# Power_5V-4A_12V-1A.net
KiCad netlist of a schematic drawn in EAGLE
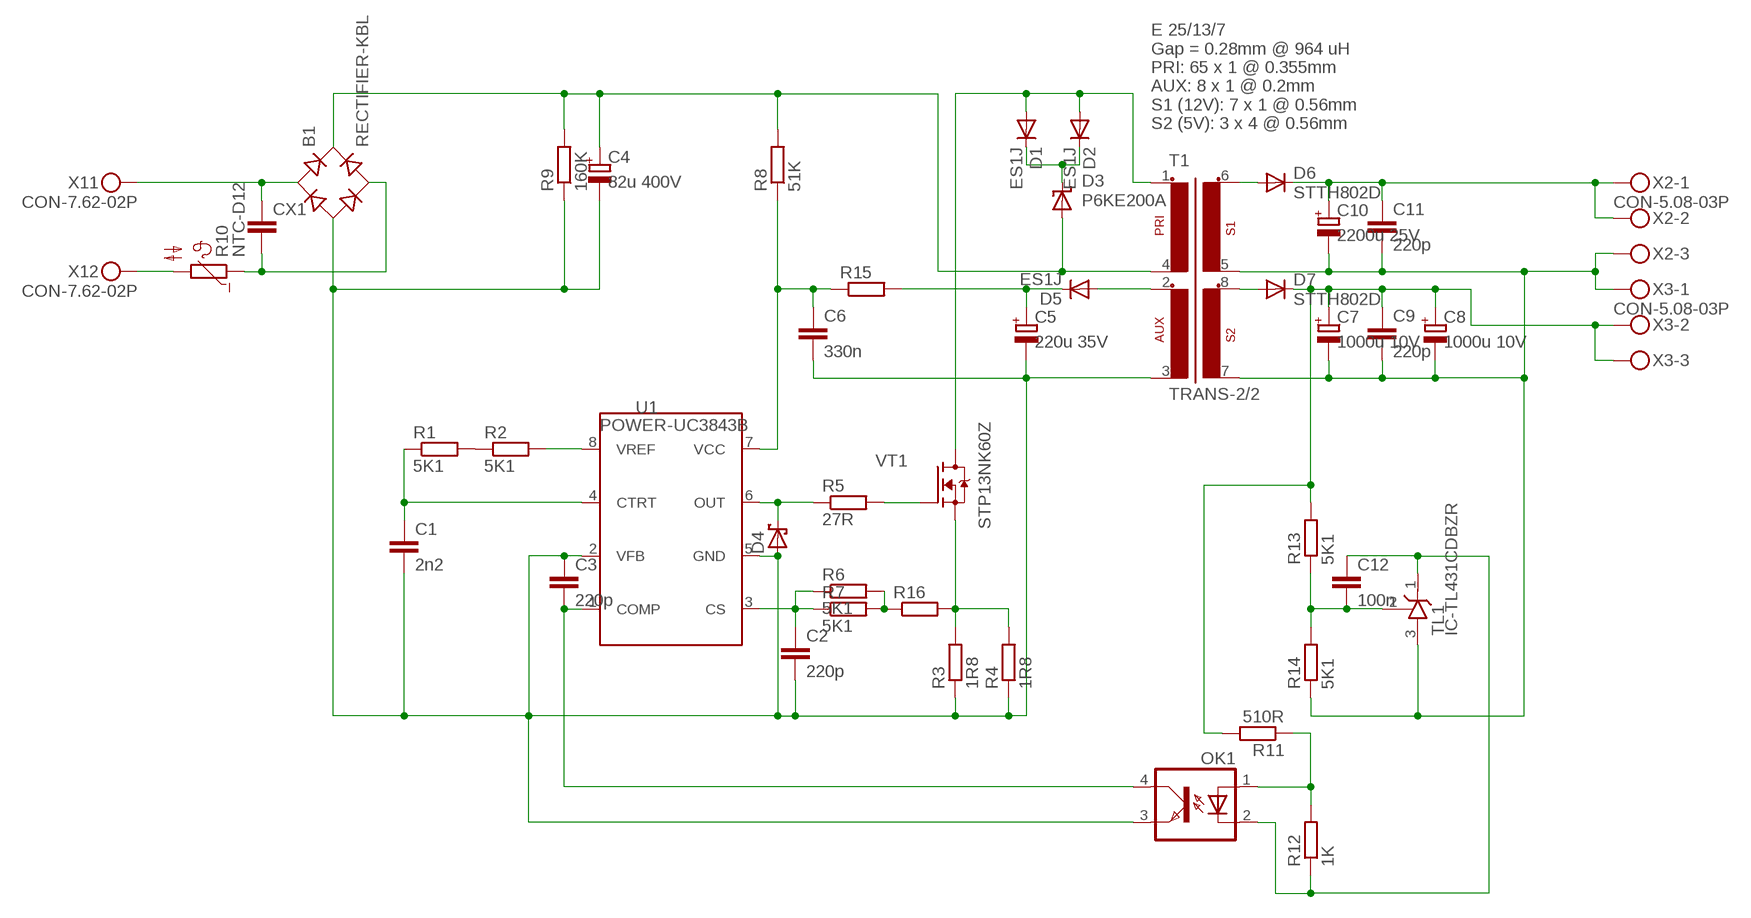
[diagram p0: schematic, sheet 1]

(export (version "E")
  (design (tool "Eeschema 10.0.6"))
  (components
    (comp (ref "B1")
      (value "RECTIFIER-KBL")
      (footprint "eagle-import:KBL")
      (libsource (lib "eagle-import") (part "RECTIFIER-KBL"))
    )
    (comp (ref "C1")
      (value "2n2")
      (footprint "eagle-import:CAP0603")
      (libsource (lib "eagle-import") (part "CAP_0603"))
    )
    (comp (ref "C2")
      (value "220p")
      (footprint "eagle-import:CAP1206")
      (libsource (lib "eagle-import") (part "CAP_1206"))
    )
    (comp (ref "C3")
      (value "220p")
      (footprint "eagle-import:CAP1206")
      (libsource (lib "eagle-import") (part "CAP_1206"))
    )
    (comp (ref "C4")
      (value "82u 400V")
      (footprint "eagle-import:C_D25-G10-CLAMP")
      (libsource (lib "eagle-import") (part "CAP-POL_E25-10-C"))
    )
    (comp (ref "C5")
      (value "220u 35V")
      (footprint "eagle-import:E3,5-8")
      (libsource (lib "eagle-import") (part "CAP-POL_E3.5-8"))
    )
    (comp (ref "C6")
      (value "330n")
      (footprint "eagle-import:CAP1206")
      (libsource (lib "eagle-import") (part "CAP_1206"))
    )
    (comp (ref "C7")
      (value "1000u 10V")
      (footprint "eagle-import:E5-10,5")
      (libsource (lib "eagle-import") (part "CAP-POL_E5-10.5"))
    )
    (comp (ref "C8")
      (value "1000u 10V")
      (footprint "eagle-import:E5-10,5")
      (libsource (lib "eagle-import") (part "CAP-POL_E5-10.5"))
    )
    (comp (ref "C9")
      (value "220p")
      (footprint "eagle-import:CAP1206")
      (libsource (lib "eagle-import") (part "CAP_1206"))
    )
    (comp (ref "C10")
      (value "2200u 25V")
      (footprint "eagle-import:E5-10,5")
      (libsource (lib "eagle-import") (part "CAP-POL_E5-10.5"))
    )
    (comp (ref "C11")
      (value "220p")
      (footprint "eagle-import:CAP1206")
      (libsource (lib "eagle-import") (part "CAP_1206"))
    )
    (comp (ref "C12")
      (value "100n")
      (footprint "eagle-import:CAP0805")
      (libsource (lib "eagle-import") (part "CAP_0805"))
    )
    (comp (ref "CX1")
      (value "CXXC15B6")
      (footprint "eagle-import:XC15B6")
      (libsource (lib "eagle-import") (part "CXXC15B6"))
    )
    (comp (ref "D1")
      (value "ES1J")
      (footprint "eagle-import:DO214AC")
      (libsource (lib "eagle-import") (part "DIODE_ES1J"))
    )
    (comp (ref "D2")
      (value "ES1J")
      (footprint "eagle-import:DO214AC")
      (libsource (lib "eagle-import") (part "DIODE_ES1J"))
    )
    (comp (ref "D3")
      (value "P6KE200A")
      (footprint "eagle-import:DO15-12")
      (libsource (lib "eagle-import") (part "SUPRESSORDO-204AC"))
    )
    (comp (ref "D4")
      (value "DIODE-SH_SMA")
      (footprint "eagle-import:DO214AC")
      (libsource (lib "eagle-import") (part "DIODE-SH_SMA"))
    )
    (comp (ref "D5")
      (value "ES1J")
      (footprint "eagle-import:DO214AC")
      (libsource (lib "eagle-import") (part "DIODE_ES1J"))
    )
    (comp (ref "D6")
      (value "STTH802D")
      (footprint "eagle-import:TO220ACS")
      (libsource (lib "eagle-import") (part "DIODE_TO-220-2"))
    )
    (comp (ref "D7")
      (value "STTH802D")
      (footprint "eagle-import:TO220ACS")
      (libsource (lib "eagle-import") (part "DIODE_TO-220-2"))
    )
    (comp (ref "OK1")
      (value "OPTOTRANSPC817")
      (footprint "eagle-import:DIL04")
      (fields (field (name "MPN") "PC817X4J000F"))
      (libsource (lib "eagle-import") (part "OPTOTRANSPC817"))
    )
    (comp (ref "R1")
      (value "5K1")
      (footprint "eagle-import:RESC1508X50")
      (libsource (lib "eagle-import") (part "R_R0603"))
    )
    (comp (ref "R2")
      (value "5K1")
      (footprint "eagle-import:RESC1508X50")
      (libsource (lib "eagle-import") (part "R_R0603"))
    )
    (comp (ref "R3")
      (value "1R8")
      (footprint "eagle-import:MF-025")
      (libsource (lib "eagle-import") (part "R_MF-025"))
    )
    (comp (ref "R4")
      (value "1R8")
      (footprint "eagle-import:MF-025")
      (libsource (lib "eagle-import") (part "R_MF-025"))
    )
    (comp (ref "R5")
      (value "27R")
      (footprint "eagle-import:RESC3216X60")
      (libsource (lib "eagle-import") (part "R_R1206"))
    )
    (comp (ref "R6")
      (value "5K1")
      (footprint "eagle-import:RESC1508X50")
      (libsource (lib "eagle-import") (part "R_R0603"))
    )
    (comp (ref "R7")
      (value "5K1")
      (footprint "eagle-import:RESC1508X50")
      (libsource (lib "eagle-import") (part "R_R0603"))
    )
    (comp (ref "R8")
      (value "51K")
      (footprint "eagle-import:MF-1")
      (libsource (lib "eagle-import") (part "R_MF-1"))
    )
    (comp (ref "R9")
      (value "160K")
      (footprint "eagle-import:MF-0125")
      (libsource (lib "eagle-import") (part "R_MF-0125"))
    )
    (comp (ref "R10")
      (value "NTC-D12")
      (footprint "eagle-import:NTC-D12")
      (libsource (lib "eagle-import") (part "NTC-D12"))
    )
    (comp (ref "R11")
      (value "510R")
      (footprint "eagle-import:RESC2012X50")
      (libsource (lib "eagle-import") (part "R_R0805"))
    )
    (comp (ref "R12")
      (value "1K")
      (footprint "eagle-import:RESC2012X50")
      (libsource (lib "eagle-import") (part "R_R0805"))
    )
    (comp (ref "R13")
      (value "5K1")
      (footprint "eagle-import:RESC1508X50")
      (libsource (lib "eagle-import") (part "R_R0603"))
    )
    (comp (ref "R14")
      (value "5K1")
      (footprint "eagle-import:RESC1508X50")
      (libsource (lib "eagle-import") (part "R_R0603"))
    )
    (comp (ref "R15")
      (value "R_R0805")
      (footprint "eagle-import:RESC2012X50")
      (libsource (lib "eagle-import") (part "R_R0805"))
    )
    (comp (ref "R16")
      (value "R_R0805")
      (footprint "eagle-import:RESC2012X50")
      (libsource (lib "eagle-import") (part "R_R0805"))
    )
    (comp (ref "T1")
      (value "TRANS-2/2")
      (footprint "eagle-import:EE25_8PIN_HORIZ")
      (libsource (lib "eagle-import") (part "TRANS-2/2"))
    )
    (comp (ref "TL1")
      (value "IC-TL431CDBZR")
      (footprint "eagle-import:SOT95P240X115-3")
      (libsource (lib "eagle-import") (part "IC-TL431CDBZR"))
    )
    (comp (ref "U1")
      (value "POWER-UC3843B")
      (footprint "eagle-import:DIP-8")
      (libsource (lib "eagle-import") (part "POWER-UC3843B"))
    )
    (comp (ref "VT1")
      (value "STP13NK60Z")
      (footprint "eagle-import:TO-220V")
      (libsource (lib "eagle-import") (part "FET-NTO-220"))
    )
    (comp (ref "X1")
      (value "CON-7.62-02P")
      (footprint "eagle-import:KF25C-7.62-02P-13")
      (libsource (lib "eagle-import") (part "CON-7.62-02P"))
    )
    (comp (ref "X2")
      (value "CON-5.08-03P")
      (footprint "eagle-import:MKDSN1,5_3-5,08")
      (libsource (lib "eagle-import") (part "CON-5.08-03P"))
    )
    (comp (ref "X3")
      (value "CON-5.08-03P")
      (footprint "eagle-import:MKDSN1,5_3-5,08")
      (libsource (lib "eagle-import") (part "CON-5.08-03P"))
    )
  )
  (nets
    (net (code "1") (name "Net-(B1-PadAC2)") (class "Default")
      (node (ref "B1") (pin "AC2") (pinfunction "AC2_AC2") (pintype "passive"))
      (node (ref "CX1") (pin "2") (pinfunction "2_2") (pintype "passive"))
      (node (ref "R10") (pin "1") (pinfunction "1_1") (pintype "passive"))
    )
    (net (code "2") (name "Net-(C5-Pad+)") (class "Default")
      (node (ref "C5") (pin "+") (pinfunction "+_+") (pintype "passive"))
      (node (ref "D5") (pin "C") (pinfunction "C_C") (pintype "passive"))
      (node (ref "R15") (pin "2") (pinfunction "2_2") (pintype "passive"))
    )
    (net (code "3") (name "Net-(D1-PadC)") (class "Default")
      (node (ref "D1") (pin "C") (pinfunction "C_C") (pintype "passive"))
      (node (ref "D2") (pin "C") (pinfunction "C_C") (pintype "passive"))
      (node (ref "D3") (pin "C") (pinfunction "C_C") (pintype "passive"))
    )
    (net (code "4") (name "Net-(OK1-A)") (class "Default")
      (node (ref "OK1") (pin "1") (pinfunction "A_1") (pintype "passive"))
      (node (ref "R11") (pin "1") (pinfunction "1_1") (pintype "passive"))
      (node (ref "R12") (pin "2") (pinfunction "2_2") (pintype "passive"))
    )
    (net (code "5") (name "Net-(OK1-C)") (class "Default")
      (node (ref "C12") (pin "1") (pinfunction "1_1") (pintype "passive"))
      (node (ref "OK1") (pin "2") (pinfunction "C_2") (pintype "passive"))
      (node (ref "R12") (pin "1") (pinfunction "1_1") (pintype "passive"))
      (node (ref "TL1") (pin "1") (pinfunction "C_1") (pintype "passive"))
    )
    (net (code "6") (name "Net-(OK1-COL)") (class "Default")
      (node (ref "C3") (pin "2") (pinfunction "2_2") (pintype "passive"))
      (node (ref "OK1") (pin "4") (pinfunction "COL_4") (pintype "passive"))
      (node (ref "U1") (pin "1") (pinfunction "COMP_1") (pintype "bidirectional"))
    )
    (net (code "7") (name "Net-(OK1-EMIT)") (class "Default")
      (node (ref "B1") (pin "-") (pinfunction "-_-") (pintype "passive"))
      (node (ref "C1") (pin "2") (pinfunction "2_2") (pintype "passive"))
      (node (ref "C2") (pin "2") (pinfunction "2_2") (pintype "passive"))
      (node (ref "C3") (pin "1") (pinfunction "1_1") (pintype "passive"))
      (node (ref "C4") (pin "-") (pinfunction "-_-") (pintype "passive"))
      (node (ref "C5") (pin "-") (pinfunction "-_-") (pintype "passive"))
      (node (ref "C6") (pin "2") (pinfunction "2_2") (pintype "passive"))
      (node (ref "D4") (pin "A") (pinfunction "A_A") (pintype "passive"))
      (node (ref "OK1") (pin "3") (pinfunction "EMIT_3") (pintype "passive"))
      (node (ref "R3") (pin "1") (pinfunction "1_1") (pintype "passive"))
      (node (ref "R4") (pin "1") (pinfunction "1_1") (pintype "passive"))
      (node (ref "R9") (pin "1") (pinfunction "1_1") (pintype "passive"))
      (node (ref "T1") (pin "3") (pinfunction "AUX-2_3") (pintype "passive"))
      (node (ref "U1") (pin "2") (pinfunction "VFB_2") (pintype "input"))
      (node (ref "U1") (pin "5") (pinfunction "GND_5") (pintype "power_in"))
    )
    (net (code "8") (name "Net-(R1-Pad2)") (class "Default")
      (node (ref "R1") (pin "2") (pinfunction "2_2") (pintype "passive"))
      (node (ref "R2") (pin "1") (pinfunction "1_1") (pintype "passive"))
    )
    (net (code "9") (name "Net-(R16-Pad1)") (class "Default")
      (node (ref "R16") (pin "1") (pinfunction "1_1") (pintype "passive"))
      (node (ref "R6") (pin "2") (pinfunction "2_2") (pintype "passive"))
      (node (ref "R7") (pin "2") (pinfunction "2_2") (pintype "passive"))
    )
    (net (code "10") (name "Net-(T1-AUX-1)") (class "Default")
      (node (ref "D5") (pin "A") (pinfunction "A_A") (pintype "passive"))
      (node (ref "T1") (pin "2") (pinfunction "AUX-1_2") (pintype "passive"))
    )
    (net (code "11") (name "Net-(T1-P1-1)") (class "Default")
      (node (ref "D1") (pin "A") (pinfunction "A_A") (pintype "passive"))
      (node (ref "D2") (pin "A") (pinfunction "A_A") (pintype "passive"))
      (node (ref "T1") (pin "1") (pinfunction "P1-1_1") (pintype "passive"))
      (node (ref "VT1") (pin "2") (pinfunction "D_2") (pintype "passive"))
    )
    (net (code "12") (name "Net-(T1-P1-2)") (class "Default")
      (node (ref "B1") (pin "+") (pinfunction "+_+") (pintype "passive"))
      (node (ref "C4") (pin "+") (pinfunction "+_+") (pintype "passive"))
      (node (ref "D3") (pin "A") (pinfunction "A_A") (pintype "passive"))
      (node (ref "R8") (pin "2") (pinfunction "2_2") (pintype "passive"))
      (node (ref "R9") (pin "2") (pinfunction "2_2") (pintype "passive"))
      (node (ref "T1") (pin "4") (pinfunction "P1-2_4") (pintype "passive"))
    )
    (net (code "13") (name "Net-(T1-S1-1)") (class "Default")
      (node (ref "D6") (pin "A") (pinfunction "A_A") (pintype "passive"))
      (node (ref "T1") (pin "6") (pinfunction "S1-1_6") (pintype "passive"))
    )
    (net (code "14") (name "Net-(T1-S1-2)") (class "Default")
      (node (ref "C10") (pin "-") (pinfunction "-_-") (pintype "passive"))
      (node (ref "C11") (pin "2") (pinfunction "2_2") (pintype "passive"))
      (node (ref "C7") (pin "-") (pinfunction "-_-") (pintype "passive"))
      (node (ref "C8") (pin "-") (pinfunction "-_-") (pintype "passive"))
      (node (ref "C9") (pin "2") (pinfunction "2_2") (pintype "passive"))
      (node (ref "R14") (pin "1") (pinfunction "1_1") (pintype "passive"))
      (node (ref "T1") (pin "5") (pinfunction "S1-2_5") (pintype "passive"))
      (node (ref "T1") (pin "7") (pinfunction "S2-2_7") (pintype "passive"))
      (node (ref "TL1") (pin "3") (pinfunction "A_3") (pintype "passive"))
      (node (ref "X2") (pin "3") (pinfunction "KL_3") (pintype "passive"))
      (node (ref "X3") (pin "1") (pinfunction "KL_1") (pintype "passive"))
    )
    (net (code "15") (name "Net-(T1-S2-1)") (class "Default")
      (node (ref "D7") (pin "A") (pinfunction "A_A") (pintype "passive"))
      (node (ref "T1") (pin "8") (pinfunction "S2-1_8") (pintype "passive"))
    )
    (net (code "16") (name "Net-(TL1-R)") (class "Default")
      (node (ref "C12") (pin "2") (pinfunction "2_2") (pintype "passive"))
      (node (ref "R13") (pin "1") (pinfunction "1_1") (pintype "passive"))
      (node (ref "R14") (pin "2") (pinfunction "2_2") (pintype "passive"))
      (node (ref "TL1") (pin "2") (pinfunction "R_2") (pintype "passive"))
    )
    (net (code "17") (name "Net-(U1-CS)") (class "Default")
      (node (ref "C2") (pin "1") (pinfunction "1_1") (pintype "passive"))
      (node (ref "R6") (pin "1") (pinfunction "1_1") (pintype "passive"))
      (node (ref "R7") (pin "1") (pinfunction "1_1") (pintype "passive"))
      (node (ref "U1") (pin "3") (pinfunction "CS_3") (pintype "input"))
    )
    (net (code "18") (name "Net-(U1-CTRT)") (class "Default")
      (node (ref "C1") (pin "1") (pinfunction "1_1") (pintype "passive"))
      (node (ref "R1") (pin "1") (pinfunction "1_1") (pintype "passive"))
      (node (ref "U1") (pin "4") (pinfunction "CTRT_4") (pintype "bidirectional"))
    )
    (net (code "19") (name "Net-(U1-OUT)") (class "Default")
      (node (ref "D4") (pin "C") (pinfunction "C_C") (pintype "passive"))
      (node (ref "R5") (pin "1") (pinfunction "1_1") (pintype "passive"))
      (node (ref "U1") (pin "6") (pinfunction "OUT_6") (pintype "output"))
    )
    (net (code "20") (name "Net-(U1-VCC)") (class "Default")
      (node (ref "C6") (pin "1") (pinfunction "1_1") (pintype "passive"))
      (node (ref "R15") (pin "1") (pinfunction "1_1") (pintype "passive"))
      (node (ref "R8") (pin "1") (pinfunction "1_1") (pintype "passive"))
      (node (ref "U1") (pin "7") (pinfunction "VCC_7") (pintype "power_in"))
    )
    (net (code "21") (name "Net-(U1-VREF)") (class "Default")
      (node (ref "R2") (pin "2") (pinfunction "2_2") (pintype "passive"))
      (node (ref "U1") (pin "8") (pinfunction "VREF_8") (pintype "power_in"))
    )
    (net (code "22") (name "Net-(VT1-G)") (class "Default")
      (node (ref "R5") (pin "2") (pinfunction "2_2") (pintype "passive"))
      (node (ref "VT1") (pin "1") (pinfunction "G_1") (pintype "passive"))
    )
    (net (code "23") (name "Net-(VT1-S)") (class "Default")
      (node (ref "R16") (pin "2") (pinfunction "2_2") (pintype "passive"))
      (node (ref "R3") (pin "2") (pinfunction "2_2") (pintype "passive"))
      (node (ref "R4") (pin "2") (pinfunction "2_2") (pintype "passive"))
      (node (ref "VT1") (pin "3") (pinfunction "S_3") (pintype "passive"))
    )
    (net (code "24") (name "Net-(X1A-KL)") (class "Default")
      (node (ref "B1") (pin "AC1") (pinfunction "AC1_AC1") (pintype "passive"))
      (node (ref "CX1") (pin "1") (pinfunction "1_1") (pintype "passive"))
      (node (ref "X1") (pin "P$1") (pinfunction "KL_P$1") (pintype "passive"))
    )
    (net (code "25") (name "Net-(X1B-KL)") (class "Default")
      (node (ref "R10") (pin "2") (pinfunction "2_2") (pintype "passive"))
      (node (ref "X1") (pin "P$2") (pinfunction "KL_P$2") (pintype "passive"))
    )
    (net (code "26") (name "Net-(X2A-KL)") (class "Default")
      (node (ref "C10") (pin "+") (pinfunction "+_+") (pintype "passive"))
      (node (ref "C11") (pin "1") (pinfunction "1_1") (pintype "passive"))
      (node (ref "D6") (pin "C") (pinfunction "C_C") (pintype "passive"))
      (node (ref "X2") (pin "1") (pinfunction "KL_1") (pintype "passive"))
      (node (ref "X2") (pin "2") (pinfunction "KL_2") (pintype "passive"))
    )
    (net (code "27") (name "Net-(X3B-KL)") (class "Default")
      (node (ref "C7") (pin "+") (pinfunction "+_+") (pintype "passive"))
      (node (ref "C8") (pin "+") (pinfunction "+_+") (pintype "passive"))
      (node (ref "C9") (pin "1") (pinfunction "1_1") (pintype "passive"))
      (node (ref "D7") (pin "C") (pinfunction "C_C") (pintype "passive"))
      (node (ref "R11") (pin "2") (pinfunction "2_2") (pintype "passive"))
      (node (ref "R13") (pin "2") (pinfunction "2_2") (pintype "passive"))
      (node (ref "X3") (pin "2") (pinfunction "KL_2") (pintype "passive"))
      (node (ref "X3") (pin "3") (pinfunction "KL_3") (pintype "passive"))
    )
  )
)
